# Top.net
KiCad netlist of a schematic drawn in Altium Designer
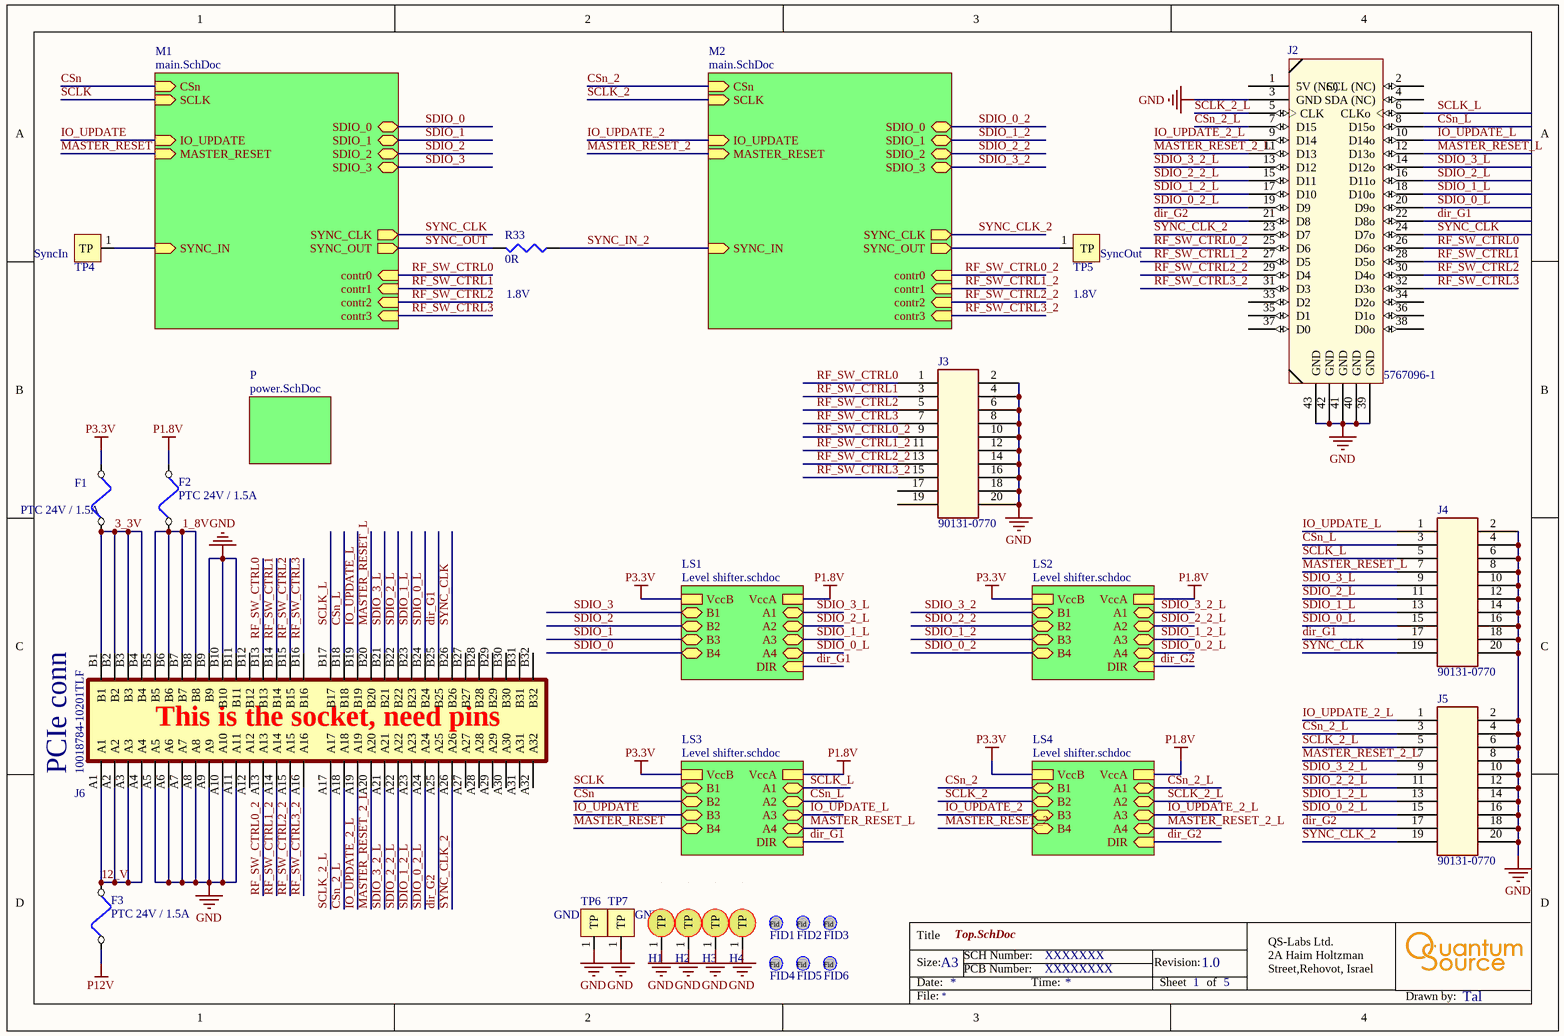
[diagram p0: Top.SchDoc]

(export (version "E")
  (design (tool "Eeschema 10.0.6"))
  (components
    (comp (ref "F1")
      (value "PTC 24V / 1.5A")
      (footprint "1812_F")
      (description "FUSE PTC 24V 1.5A POLYFUSE 1812")
      (fields
        (field (name "MANUFACTURER") "Littelfuse Inc")
        (field (name "MANUFACTURER PART NUMBER") "1812L150/24MR")
      )
      (libsource (lib "DPB_spliter") (part "1812L150/24MR"))
    )
    (comp (ref "F2")
      (value "PTC 24V / 1.5A")
      (footprint "1812_F")
      (description "FUSE PTC 24V 1.5A POLYFUSE 1812")
      (fields
        (field (name "MANUFACTURER") "Littelfuse Inc")
        (field (name "MANUFACTURER PART NUMBER") "1812L150/24MR")
      )
      (libsource (lib "DPB_spliter") (part "1812L150/24MR"))
    )
    (comp (ref "F3")
      (value "PTC 24V / 1.5A")
      (footprint "1812_F")
      (description "FUSE PTC 24V 1.5A POLYFUSE 1812")
      (fields
        (field (name "MANUFACTURER") "Littelfuse Inc")
        (field (name "MANUFACTURER PART NUMBER") "1812L150/24MR")
      )
      (libsource (lib "DPB_spliter") (part "1812L150/24MR"))
    )
    (comp (ref "FID1")
      (value "Fiducial")
      (footprint "Fiducial")
      (libsource (lib "DDS_PCB") (part "Fiducial"))
    )
    (comp (ref "FID2")
      (value "Fiducial")
      (footprint "Fiducial")
      (libsource (lib "DDS_PCB") (part "Fiducial"))
    )
    (comp (ref "FID3")
      (value "Fiducial")
      (footprint "Fiducial")
      (libsource (lib "DDS_PCB") (part "Fiducial"))
    )
    (comp (ref "FID4")
      (value "Fiducial")
      (footprint "Fiducial")
      (libsource (lib "DDS_PCB") (part "Fiducial"))
    )
    (comp (ref "FID5")
      (value "Fiducial")
      (footprint "Fiducial")
      (libsource (lib "DDS_PCB") (part "Fiducial"))
    )
    (comp (ref "FID6")
      (value "Fiducial")
      (footprint "Fiducial")
      (libsource (lib "DDS_PCB") (part "Fiducial"))
    )
    (comp (ref "H1")
      (value "Hole 3mm")
      (footprint "hole 3mm")
      (description "hole 3mm")
      (libsource (lib "L_SCH_Misc") (part "Hole 3mm"))
    )
    (comp (ref "H2")
      (value "Hole 3mm")
      (footprint "hole 3mm")
      (description "hole 3mm")
      (libsource (lib "L_SCH_Misc") (part "Hole 3mm"))
    )
    (comp (ref "H3")
      (value "Hole 3mm")
      (footprint "hole 3mm")
      (description "hole 3mm")
      (libsource (lib "L_SCH_Misc") (part "Hole 3mm"))
    )
    (comp (ref "H4")
      (value "Hole 3mm")
      (footprint "hole 3mm")
      (description "hole 3mm")
      (libsource (lib "L_SCH_Misc") (part "Hole 3mm"))
    )
    (comp (ref "J2")
      (value "5767096-1")
      (footprint "MICTOR-38_PIN")
      (description "CONN MICTOR 38POS .025 VERT SMD")
      (fields
        (field (name "MANUFACTURER") "TE Connectivity")
        (field (name "MANUFACTURER PART NUMBER") "5767096-1")
      )
      (libsource (lib "L_SCH_J_Z") (part "5767096-1"))
    )
    (comp (ref "J3")
      (value "90131-0770")
      (footprint "HEADER_10x2")
      (description "CONN HEADER 20 TH")
      (fields
        (field (name "MANUFACTURER") "Molex Connector Corporation")
        (field (name "MANUFACTURER PART NUMBER") "90131-0770")
      )
      (libsource (lib "L_SCH_J_Z") (part "90131-0770"))
    )
    (comp (ref "J4")
      (value "90131-0770")
      (footprint "HEADER_10x2")
      (description "CONN HEADER 20 TH")
      (fields
        (field (name "MANUFACTURER") "Molex Connector Corporation")
        (field (name "MANUFACTURER PART NUMBER") "90131-0770")
      )
      (libsource (lib "L_SCH_J_Z") (part "90131-0770"))
    )
    (comp (ref "J5")
      (value "90131-0770")
      (footprint "HEADER_10x2")
      (description "CONN HEADER 20 TH")
      (fields
        (field (name "MANUFACTURER") "Molex Connector Corporation")
        (field (name "MANUFACTURER PART NUMBER") "90131-0770")
      )
      (libsource (lib "L_SCH_J_Z") (part "90131-0770"))
    )
    (comp (ref "J6")
      (value "10018784-10201TLF")
      (footprint "PCIE_8LANE_EDGE")
      (description "64 Position Female Connector PCI Expressâ„¢ Gold 0.039 _1.00mm_ Black")
      (fields (field (name "MF") "Amphenol ICC"))
      (libsource (lib "10018784-10201TLF") (part "10018784-10201TLF"))
    )
    (comp (ref "R33")
      (value "0R")
      (footprint "R0402")
      (description "RES 0 OHM 1/10W 1% 0402 SMD")
      (fields
        (field (name "MANUFACTURER PART NUMBER") "ERJ-2RKF1000X")
        (field (name "MANUFACTURER") "Panasonic Electronic Components")
      )
      (libsource (lib "L_SCH_R") (part "RES 100 OHM 1/10W 1% 0402 SMD"))
    )
    (comp (ref "TP4")
      (value "SyncIn")
      (footprint "Landa_PCB:TP_2x1.8")
      (description "TP PC MINIATURE SMT")
      (fields
        (field (name "MANUFACTURER") "Keystone Electronics")
        (field (name "MANUFACTURER PART NUMBER") "5015")
      )
      (libsource (lib "") (part "TP mini_2_1"))
    )
    (comp (ref "TP5")
      (value "SyncOut")
      (footprint "Landa_PCB:TP_2x1.8")
      (description "TP PC MINIATURE SMT")
      (fields
        (field (name "MANUFACTURER") "Keystone Electronics")
        (field (name "MANUFACTURER PART NUMBER") "5015")
      )
      (libsource (lib "DPB_spliter") (part "TP mini_2"))
    )
    (comp (ref "TP6")
      (value "GND")
      (footprint "Landa_PCB:TP_2x1.8")
      (description "TP PC MINIATURE SMT")
      (fields
        (field (name "MANUFACTURER") "Keystone Electronics")
        (field (name "MANUFACTURER PART NUMBER") "5015")
      )
      (libsource (lib "") (part "TP mini_2_2"))
    )
    (comp (ref "TP7")
      (value "GND")
      (footprint "Landa_PCB:TP_2x1.8")
      (description "TP PC MINIATURE SMT")
      (fields
        (field (name "MANUFACTURER") "Keystone Electronics")
        (field (name "MANUFACTURER PART NUMBER") "5015")
      )
      (libsource (lib "DPB_spliter") (part "TP mini_1"))
    )
  )
  (nets
    (net (code "1") (name "/1_8V") (class "Default")
      (node (ref "F2") (pin "1") (pinfunction "1_1") (pintype "passive"))
      (node (ref "J6") (pin "B5") (pinfunction "B5_B5") (pintype "passive"))
      (node (ref "J6") (pin "B6") (pinfunction "B6_B6") (pintype "passive"))
      (node (ref "J6") (pin "B7") (pinfunction "B7_B7") (pintype "passive"))
      (node (ref "J6") (pin "B8") (pinfunction "B8_B8") (pintype "passive"))
    )
    (net (code "2") (name "/3_3V") (class "Default")
      (node (ref "F1") (pin "1") (pinfunction "1_1") (pintype "passive"))
      (node (ref "J6") (pin "B1") (pinfunction "B1_B1") (pintype "passive"))
      (node (ref "J6") (pin "B2") (pinfunction "B2_B2") (pintype "passive"))
      (node (ref "J6") (pin "B3") (pinfunction "B3_B3") (pintype "passive"))
      (node (ref "J6") (pin "B4") (pinfunction "B4_B4") (pintype "passive"))
    )
    (net (code "3") (name "/12_V") (class "Default")
      (node (ref "F3") (pin "2") (pinfunction "2_2") (pintype "passive"))
      (node (ref "J6") (pin "A1") (pinfunction "A1_A1") (pintype "passive"))
      (node (ref "J6") (pin "A2") (pinfunction "A2_A2") (pintype "passive"))
      (node (ref "J6") (pin "A3") (pinfunction "A3_A3") (pintype "passive"))
      (node (ref "J6") (pin "A4") (pinfunction "A4_A4") (pintype "passive"))
    )
    (net (code "6") (name "/CSn_2_L") (class "Default")
      (node (ref "J2") (pin "7") (pinfunction "D15_7") (pintype "bidirectional"))
      (node (ref "J5") (pin "3") (pinfunction "3_3") (pintype "passive"))
      (node (ref "J6") (pin "A18") (pinfunction "A18_A18") (pintype "passive"))
    )
    (net (code "7") (name "/CSn_L") (class "Default")
      (node (ref "J2") (pin "8") (pinfunction "D15o_8") (pintype "bidirectional"))
      (node (ref "J4") (pin "3") (pinfunction "3_3") (pintype "passive"))
      (node (ref "J6") (pin "B18") (pinfunction "B18_B18") (pintype "passive"))
    )
    (net (code "10") (name "/IO_UPDATE_2_L") (class "Default")
      (node (ref "J2") (pin "9") (pinfunction "D14_9") (pintype "bidirectional"))
      (node (ref "J5") (pin "1") (pinfunction "1_1") (pintype "passive"))
      (node (ref "J6") (pin "A19") (pinfunction "A19_A19") (pintype "passive"))
    )
    (net (code "11") (name "/IO_UPDATE_L") (class "Default")
      (node (ref "J2") (pin "10") (pinfunction "D14o_10") (pintype "bidirectional"))
      (node (ref "J4") (pin "1") (pinfunction "1_1") (pintype "passive"))
      (node (ref "J6") (pin "B19") (pinfunction "B19_B19") (pintype "passive"))
    )
    (net (code "14") (name "/MASTER_RESET_2_L") (class "Default")
      (node (ref "J2") (pin "11") (pinfunction "D13_11") (pintype "bidirectional"))
      (node (ref "J5") (pin "7") (pinfunction "7_7") (pintype "passive"))
      (node (ref "J6") (pin "A20") (pinfunction "A20_A20") (pintype "passive"))
    )
    (net (code "15") (name "/MASTER_RESET_L") (class "Default")
      (node (ref "J2") (pin "12") (pinfunction "D13o_12") (pintype "bidirectional"))
      (node (ref "J4") (pin "7") (pinfunction "7_7") (pintype "passive"))
      (node (ref "J6") (pin "B20") (pinfunction "B20_B20") (pintype "passive"))
    )
    (net (code "16") (name "/RF_SW_CTRL0") (class "Default")
      (node (ref "J2") (pin "26") (pinfunction "D6o_26") (pintype "bidirectional"))
      (node (ref "J3") (pin "1") (pinfunction "1_1") (pintype "passive"))
      (node (ref "J6") (pin "B13") (pinfunction "B13_B13") (pintype "passive"))
    )
    (net (code "17") (name "/RF_SW_CTRL0_2") (class "Default")
      (node (ref "J2") (pin "25") (pinfunction "D6_25") (pintype "bidirectional"))
      (node (ref "J3") (pin "9") (pinfunction "9_9") (pintype "passive"))
      (node (ref "J6") (pin "A13") (pinfunction "A13_A13") (pintype "passive"))
    )
    (net (code "18") (name "/RF_SW_CTRL1") (class "Default")
      (node (ref "J2") (pin "28") (pinfunction "D5o_28") (pintype "bidirectional"))
      (node (ref "J3") (pin "3") (pinfunction "3_3") (pintype "passive"))
      (node (ref "J6") (pin "B14") (pinfunction "B14_B14") (pintype "passive"))
    )
    (net (code "19") (name "/RF_SW_CTRL1_2") (class "Default")
      (node (ref "J2") (pin "27") (pinfunction "D5_27") (pintype "bidirectional"))
      (node (ref "J3") (pin "11") (pinfunction "11_11") (pintype "passive"))
      (node (ref "J6") (pin "A14") (pinfunction "A14_A14") (pintype "passive"))
    )
    (net (code "20") (name "/RF_SW_CTRL2") (class "Default")
      (node (ref "J2") (pin "30") (pinfunction "D4o_30") (pintype "bidirectional"))
      (node (ref "J3") (pin "5") (pinfunction "5_5") (pintype "passive"))
      (node (ref "J6") (pin "B15") (pinfunction "B15_B15") (pintype "passive"))
    )
    (net (code "21") (name "/RF_SW_CTRL2_2") (class "Default")
      (node (ref "J2") (pin "29") (pinfunction "D4_29") (pintype "bidirectional"))
      (node (ref "J3") (pin "13") (pinfunction "13_13") (pintype "passive"))
      (node (ref "J6") (pin "A15") (pinfunction "A15_A15") (pintype "passive"))
    )
    (net (code "22") (name "/RF_SW_CTRL3") (class "Default")
      (node (ref "J2") (pin "32") (pinfunction "D3o_32") (pintype "bidirectional"))
      (node (ref "J3") (pin "7") (pinfunction "7_7") (pintype "passive"))
      (node (ref "J6") (pin "B16") (pinfunction "B16_B16") (pintype "passive"))
    )
    (net (code "23") (name "/RF_SW_CTRL3_2") (class "Default")
      (node (ref "J2") (pin "31") (pinfunction "D3_31") (pintype "bidirectional"))
      (node (ref "J3") (pin "15") (pinfunction "15_15") (pintype "passive"))
      (node (ref "J6") (pin "A16") (pinfunction "A16_A16") (pintype "passive"))
    )
    (net (code "26") (name "/SCLK_2_L") (class "Default")
      (node (ref "J2") (pin "5") (pinfunction "CLK_5") (pintype "bidirectional"))
      (node (ref "J5") (pin "5") (pinfunction "5_5") (pintype "passive"))
      (node (ref "J6") (pin "A17") (pinfunction "A17_A17") (pintype "passive"))
    )
    (net (code "27") (name "/SCLK_L") (class "Default")
      (node (ref "J2") (pin "6") (pinfunction "CLKo_6") (pintype "bidirectional"))
      (node (ref "J4") (pin "5") (pinfunction "5_5") (pintype "passive"))
      (node (ref "J6") (pin "B17") (pinfunction "B17_B17") (pintype "passive"))
    )
    (net (code "30") (name "/SDIO_0_2_L") (class "Default")
      (node (ref "J2") (pin "19") (pinfunction "D9_19") (pintype "bidirectional"))
      (node (ref "J5") (pin "15") (pinfunction "15_15") (pintype "passive"))
      (node (ref "J6") (pin "A24") (pinfunction "A24_A24") (pintype "passive"))
    )
    (net (code "31") (name "/SDIO_0_L") (class "Default")
      (node (ref "J2") (pin "20") (pinfunction "D9o_20") (pintype "bidirectional"))
      (node (ref "J4") (pin "15") (pinfunction "15_15") (pintype "passive"))
      (node (ref "J6") (pin "B24") (pinfunction "B24_B24") (pintype "passive"))
    )
    (net (code "34") (name "/SDIO_1_2_L") (class "Default")
      (node (ref "J2") (pin "17") (pinfunction "D10_17") (pintype "bidirectional"))
      (node (ref "J5") (pin "13") (pinfunction "13_13") (pintype "passive"))
      (node (ref "J6") (pin "A23") (pinfunction "A23_A23") (pintype "passive"))
    )
    (net (code "35") (name "/SDIO_1_L") (class "Default")
      (node (ref "J2") (pin "18") (pinfunction "D10o_18") (pintype "bidirectional"))
      (node (ref "J4") (pin "13") (pinfunction "13_13") (pintype "passive"))
      (node (ref "J6") (pin "B23") (pinfunction "B23_B23") (pintype "passive"))
    )
    (net (code "38") (name "/SDIO_2_2_L") (class "Default")
      (node (ref "J2") (pin "15") (pinfunction "D11_15") (pintype "bidirectional"))
      (node (ref "J5") (pin "11") (pinfunction "11_11") (pintype "passive"))
      (node (ref "J6") (pin "A22") (pinfunction "A22_A22") (pintype "passive"))
    )
    (net (code "39") (name "/SDIO_2_L") (class "Default")
      (node (ref "J2") (pin "16") (pinfunction "D11o_16") (pintype "bidirectional"))
      (node (ref "J4") (pin "11") (pinfunction "11_11") (pintype "passive"))
      (node (ref "J6") (pin "B22") (pinfunction "B22_B22") (pintype "passive"))
    )
    (net (code "42") (name "/SDIO_3_2_L") (class "Default")
      (node (ref "J2") (pin "13") (pinfunction "D12_13") (pintype "bidirectional"))
      (node (ref "J5") (pin "9") (pinfunction "9_9") (pintype "passive"))
      (node (ref "J6") (pin "A21") (pinfunction "A21_A21") (pintype "passive"))
    )
    (net (code "43") (name "/SDIO_3_L") (class "Default")
      (node (ref "J2") (pin "14") (pinfunction "D12o_14") (pintype "bidirectional"))
      (node (ref "J4") (pin "9") (pinfunction "9_9") (pintype "passive"))
      (node (ref "J6") (pin "B21") (pinfunction "B21_B21") (pintype "passive"))
    )
    (net (code "44") (name "/SYNC_CLK") (class "Default")
      (node (ref "J2") (pin "24") (pinfunction "D7o_24") (pintype "bidirectional"))
      (node (ref "J4") (pin "19") (pinfunction "19_19") (pintype "passive"))
      (node (ref "J6") (pin "B26") (pinfunction "B26_B26") (pintype "passive"))
    )
    (net (code "45") (name "/SYNC_CLK_2") (class "Default")
      (node (ref "J2") (pin "23") (pinfunction "D7_23") (pintype "bidirectional"))
      (node (ref "J5") (pin "19") (pinfunction "19_19") (pintype "passive"))
      (node (ref "J6") (pin "A26") (pinfunction "A26_A26") (pintype "passive"))
    )
    (net (code "46") (name "/SYNC_IN") (class "Default")
      (node (ref "TP4") (pin "1") (pinfunction "TP_1") (pintype "passive"))
    )
    (net (code "47") (name "/SYNC_IN_2") (class "Default")
      (node (ref "R33") (pin "1") (pinfunction "1_1") (pintype "passive"))
    )
    (net (code "48") (name "/SYNC_OUT") (class "Default")
      (node (ref "R33") (pin "2") (pinfunction "2_2") (pintype "passive"))
    )
    (net (code "49") (name "/SYNC_OUT_1") (class "Default")
      (node (ref "TP5") (pin "1") (pinfunction "TP_1") (pintype "passive"))
    )
    (net (code "50") (name "/dir_G1") (class "Default")
      (node (ref "J2") (pin "22") (pinfunction "D8o_22") (pintype "bidirectional"))
      (node (ref "J4") (pin "17") (pinfunction "17_17") (pintype "passive"))
      (node (ref "J6") (pin "B25") (pinfunction "B25_B25") (pintype "passive"))
    )
    (net (code "51") (name "/dir_G2") (class "Default")
      (node (ref "J2") (pin "21") (pinfunction "D8_21") (pintype "bidirectional"))
      (node (ref "J5") (pin "17") (pinfunction "17_17") (pintype "passive"))
      (node (ref "J6") (pin "A25") (pinfunction "A25_A25") (pintype "passive"))
    )
    (net (code "52") (name "GND") (class "Default")
      (node (ref "H1") (pin "1") (pinfunction "TP_1") (pintype "passive"))
      (node (ref "H2") (pin "1") (pinfunction "TP_1") (pintype "passive"))
      (node (ref "H3") (pin "1") (pinfunction "TP_1") (pintype "passive"))
      (node (ref "H4") (pin "1") (pinfunction "TP_1") (pintype "passive"))
      (node (ref "J2") (pin "3") (pinfunction "GND_3") (pintype "power_in"))
      (node (ref "J2") (pin "39") (pinfunction "GND_39") (pintype "power_in"))
      (node (ref "J2") (pin "40") (pinfunction "GND_40") (pintype "power_in"))
      (node (ref "J2") (pin "41") (pinfunction "GND_41") (pintype "power_in"))
      (node (ref "J2") (pin "42") (pinfunction "GND_42") (pintype "power_in"))
      (node (ref "J2") (pin "43") (pinfunction "GND_43") (pintype "power_in"))
      (node (ref "J3") (pin "10") (pinfunction "10_10") (pintype "passive"))
      (node (ref "J3") (pin "12") (pinfunction "12_12") (pintype "passive"))
      (node (ref "J3") (pin "14") (pinfunction "14_14") (pintype "passive"))
      (node (ref "J3") (pin "16") (pinfunction "16_16") (pintype "passive"))
      (node (ref "J3") (pin "18") (pinfunction "18_18") (pintype "passive"))
      (node (ref "J3") (pin "2") (pinfunction "2_2") (pintype "passive"))
      (node (ref "J3") (pin "20") (pinfunction "20_20") (pintype "passive"))
      (node (ref "J3") (pin "4") (pinfunction "4_4") (pintype "passive"))
      (node (ref "J3") (pin "6") (pinfunction "6_6") (pintype "passive"))
      (node (ref "J3") (pin "8") (pinfunction "8_8") (pintype "passive"))
      (node (ref "J4") (pin "10") (pinfunction "10_10") (pintype "passive"))
      (node (ref "J4") (pin "12") (pinfunction "12_12") (pintype "passive"))
      (node (ref "J4") (pin "14") (pinfunction "14_14") (pintype "passive"))
      (node (ref "J4") (pin "16") (pinfunction "16_16") (pintype "passive"))
      (node (ref "J4") (pin "18") (pinfunction "18_18") (pintype "passive"))
      (node (ref "J4") (pin "2") (pinfunction "2_2") (pintype "passive"))
      (node (ref "J4") (pin "20") (pinfunction "20_20") (pintype "passive"))
      (node (ref "J4") (pin "4") (pinfunction "4_4") (pintype "passive"))
      (node (ref "J4") (pin "6") (pinfunction "6_6") (pintype "passive"))
      (node (ref "J4") (pin "8") (pinfunction "8_8") (pintype "passive"))
      (node (ref "J5") (pin "10") (pinfunction "10_10") (pintype "passive"))
      (node (ref "J5") (pin "12") (pinfunction "12_12") (pintype "passive"))
      (node (ref "J5") (pin "14") (pinfunction "14_14") (pintype "passive"))
      (node (ref "J5") (pin "16") (pinfunction "16_16") (pintype "passive"))
      (node (ref "J5") (pin "18") (pinfunction "18_18") (pintype "passive"))
      (node (ref "J5") (pin "2") (pinfunction "2_2") (pintype "passive"))
      (node (ref "J5") (pin "20") (pinfunction "20_20") (pintype "passive"))
      (node (ref "J5") (pin "4") (pinfunction "4_4") (pintype "passive"))
      (node (ref "J5") (pin "6") (pinfunction "6_6") (pintype "passive"))
      (node (ref "J5") (pin "8") (pinfunction "8_8") (pintype "passive"))
      (node (ref "J6") (pin "A10") (pinfunction "A10_A10") (pintype "passive"))
      (node (ref "J6") (pin "A11") (pinfunction "A11_A11") (pintype "passive"))
      (node (ref "J6") (pin "A5") (pinfunction "A5_A5") (pintype "passive"))
      (node (ref "J6") (pin "A6") (pinfunction "A6_A6") (pintype "passive"))
      (node (ref "J6") (pin "A7") (pinfunction "A7_A7") (pintype "passive"))
      (node (ref "J6") (pin "A8") (pinfunction "A8_A8") (pintype "passive"))
      (node (ref "J6") (pin "A9") (pinfunction "A9_A9") (pintype "passive"))
      (node (ref "J6") (pin "B10") (pinfunction "B10_B10") (pintype "passive"))
      (node (ref "J6") (pin "B11") (pinfunction "B11_B11") (pintype "passive"))
      (node (ref "J6") (pin "B9") (pinfunction "B9_B9") (pintype "passive"))
      (node (ref "TP6") (pin "1") (pinfunction "TP_1") (pintype "passive"))
      (node (ref "TP7") (pin "1") (pinfunction "TP_1") (pintype "passive"))
    )
    (net (code "53") (name "P1.8V") (class "Default")
      (node (ref "F2") (pin "2") (pinfunction "2_2") (pintype "passive"))
    )
    (net (code "54") (name "P3.3V") (class "Default")
      (node (ref "F1") (pin "2") (pinfunction "2_2") (pintype "passive"))
    )
    (net (code "55") (name "P12V") (class "Default")
      (node (ref "F3") (pin "1") (pinfunction "1_1") (pintype "passive"))
    )
    (net (code "56") (name "unconnected-(J2-5V_(NC)-Pad1)") (class "Default")
      (node (ref "J2") (pin "1") (pinfunction "5V_(NC)_1") (pintype "power_in"))
    )
    (net (code "57") (name "unconnected-(J2-D0-Pad37)") (class "Default")
      (node (ref "J2") (pin "37") (pinfunction "D0_37") (pintype "bidirectional"))
    )
    (net (code "58") (name "unconnected-(J2-D0o-Pad38)") (class "Default")
      (node (ref "J2") (pin "38") (pinfunction "D0o_38") (pintype "bidirectional"))
    )
    (net (code "59") (name "unconnected-(J2-D1-Pad35)") (class "Default")
      (node (ref "J2") (pin "35") (pinfunction "D1_35") (pintype "bidirectional"))
    )
    (net (code "60") (name "unconnected-(J2-D1o-Pad36)") (class "Default")
      (node (ref "J2") (pin "36") (pinfunction "D1o_36") (pintype "bidirectional"))
    )
    (net (code "61") (name "unconnected-(J2-D2-Pad33)") (class "Default")
      (node (ref "J2") (pin "33") (pinfunction "D2_33") (pintype "bidirectional"))
    )
    (net (code "62") (name "unconnected-(J2-D2o-Pad34)") (class "Default")
      (node (ref "J2") (pin "34") (pinfunction "D2o_34") (pintype "bidirectional"))
    )
    (net (code "63") (name "unconnected-(J2-SCL_(NC)-Pad2)") (class "Default")
      (node (ref "J2") (pin "2") (pinfunction "SCL_(NC)_2") (pintype "bidirectional"))
    )
    (net (code "64") (name "unconnected-(J2-SDA_(NC)-Pad4)") (class "Default")
      (node (ref "J2") (pin "4") (pinfunction "SDA_(NC)_4") (pintype "bidirectional"))
    )
    (net (code "65") (name "unconnected-(J3-Pad17)") (class "Default")
      (node (ref "J3") (pin "17") (pinfunction "17_17") (pintype "passive"))
    )
    (net (code "66") (name "unconnected-(J3-Pad19)") (class "Default")
      (node (ref "J3") (pin "19") (pinfunction "19_19") (pintype "passive"))
    )
    (net (code "67") (name "unconnected-(J6-PadA12)") (class "Default")
      (node (ref "J6") (pin "A12") (pinfunction "A12_A12") (pintype "passive"))
    )
    (net (code "68") (name "unconnected-(J6-PadA27)") (class "Default")
      (node (ref "J6") (pin "A27") (pinfunction "A27_A27") (pintype "passive"))
    )
    (net (code "69") (name "unconnected-(J6-PadA28)") (class "Default")
      (node (ref "J6") (pin "A28") (pinfunction "A28_A28") (pintype "passive"))
    )
    (net (code "70") (name "unconnected-(J6-PadA29)") (class "Default")
      (node (ref "J6") (pin "A29") (pinfunction "A29_A29") (pintype "passive"))
    )
    (net (code "71") (name "unconnected-(J6-PadA30)") (class "Default")
      (node (ref "J6") (pin "A30") (pinfunction "A30_A30") (pintype "passive"))
    )
    (net (code "72") (name "unconnected-(J6-PadA31)") (class "Default")
      (node (ref "J6") (pin "A31") (pinfunction "A31_A31") (pintype "passive"))
    )
    (net (code "73") (name "unconnected-(J6-PadA32)") (class "Default")
      (node (ref "J6") (pin "A32") (pinfunction "A32_A32") (pintype "passive"))
    )
    (net (code "74") (name "unconnected-(J6-PadB12)") (class "Default")
      (node (ref "J6") (pin "B12") (pinfunction "B12_B12") (pintype "passive"))
    )
    (net (code "75") (name "unconnected-(J6-PadB27)") (class "Default")
      (node (ref "J6") (pin "B27") (pinfunction "B27_B27") (pintype "passive"))
    )
    (net (code "76") (name "unconnected-(J6-PadB28)") (class "Default")
      (node (ref "J6") (pin "B28") (pinfunction "B28_B28") (pintype "passive"))
    )
    (net (code "77") (name "unconnected-(J6-PadB29)") (class "Default")
      (node (ref "J6") (pin "B29") (pinfunction "B29_B29") (pintype "passive"))
    )
    (net (code "78") (name "unconnected-(J6-PadB30)") (class "Default")
      (node (ref "J6") (pin "B30") (pinfunction "B30_B30") (pintype "passive"))
    )
    (net (code "79") (name "unconnected-(J6-PadB31)") (class "Default")
      (node (ref "J6") (pin "B31") (pinfunction "B31_B31") (pintype "passive"))
    )
    (net (code "80") (name "unconnected-(J6-PadB32)") (class "Default")
      (node (ref "J6") (pin "B32") (pinfunction "B32_B32") (pintype "passive"))
    )
  )
)
